# logger.net
KiCad netlist of a schematic drawn in EAGLE
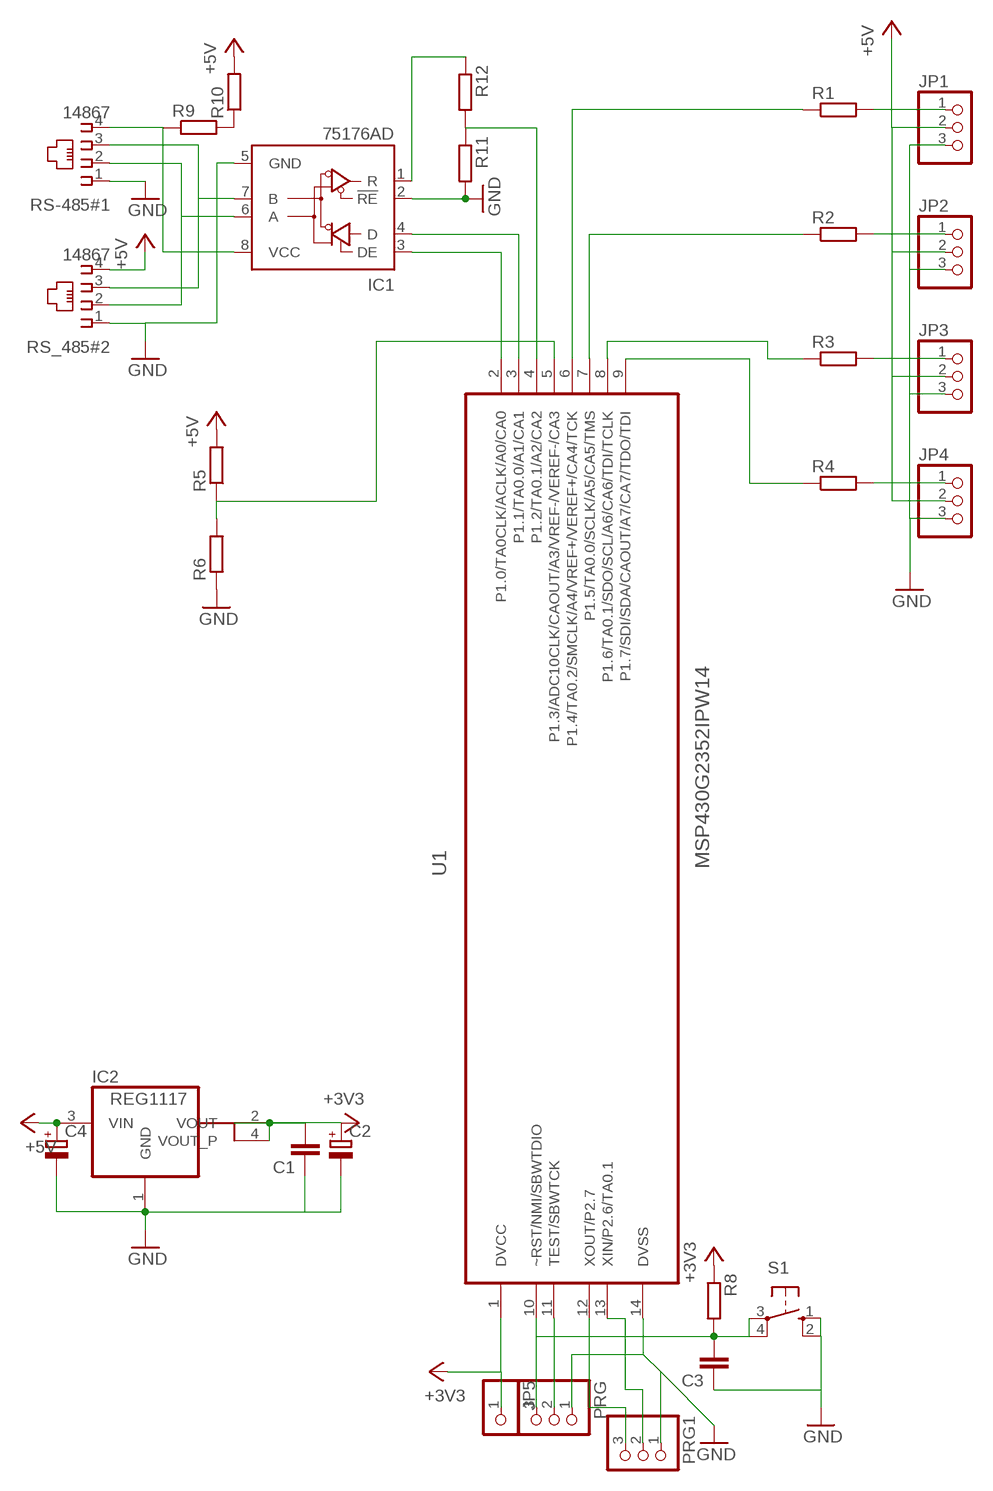
[diagram p0: schematic, sheet 1]

(export (version "E")
  (design (tool "Eeschema 10.0.6"))
  (components
    (comp (ref "C1")
      (value "C-EUC0805")
      (footprint "eagle-import:C0805")
      (libsource (lib "eagle-import") (part "C-EUC0805"))
    )
    (comp (ref "C2")
      (value "CPOL-EUE2,5-6E")
      (footprint "eagle-import:E2,5-6E")
      (libsource (lib "eagle-import") (part "CPOL-EUE2,5-6E"))
    )
    (comp (ref "C3")
      (value "C-EUC0805")
      (footprint "eagle-import:C0805")
      (libsource (lib "eagle-import") (part "C-EUC0805"))
    )
    (comp (ref "C4")
      (value "CPOL-EUE2,5-6E")
      (footprint "eagle-import:E2,5-6E")
      (libsource (lib "eagle-import") (part "CPOL-EUE2,5-6E"))
    )
    (comp (ref "IC1")
      (value "75176AD")
      (footprint "eagle-import:D_R-PDSO-G8")
      (libsource (lib "eagle-import") (part "75176AD"))
    )
    (comp (ref "IC2")
      (value "REG1117")
      (footprint "eagle-import:SOT223")
      (libsource (lib "eagle-import") (part "REG1117"))
    )
    (comp (ref "JP1")
      (value "PINHD-1X3")
      (footprint "eagle-import:1X03")
      (libsource (lib "eagle-import") (part "PINHD-1X3"))
    )
    (comp (ref "JP2")
      (value "PINHD-1X3")
      (footprint "eagle-import:1X03")
      (libsource (lib "eagle-import") (part "PINHD-1X3"))
    )
    (comp (ref "JP3")
      (value "PINHD-1X3")
      (footprint "eagle-import:1X03")
      (libsource (lib "eagle-import") (part "PINHD-1X3"))
    )
    (comp (ref "JP4")
      (value "PINHD-1X3")
      (footprint "eagle-import:1X03")
      (libsource (lib "eagle-import") (part "PINHD-1X3"))
    )
    (comp (ref "JP5")
      (value "PINHD-1X1")
      (footprint "eagle-import:1X01")
      (libsource (lib "eagle-import") (part "PINHD-1X1"))
    )
    (comp (ref "PRG")
      (value "PINHD-1X3")
      (footprint "eagle-import:1X03")
      (libsource (lib "eagle-import") (part "PINHD-1X3"))
    )
    (comp (ref "PRG1")
      (value "PINHD-1X3")
      (footprint "eagle-import:1X03")
      (libsource (lib "eagle-import") (part "PINHD-1X3"))
    )
    (comp (ref "R1")
      (value "R-EU_R0805")
      (footprint "eagle-import:R0805")
      (libsource (lib "eagle-import") (part "R-EU_R0805"))
    )
    (comp (ref "R2")
      (value "R-EU_R0805")
      (footprint "eagle-import:R0805")
      (libsource (lib "eagle-import") (part "R-EU_R0805"))
    )
    (comp (ref "R3")
      (value "R-EU_R0805")
      (footprint "eagle-import:R0805")
      (libsource (lib "eagle-import") (part "R-EU_R0805"))
    )
    (comp (ref "R4")
      (value "R-EU_R0805")
      (footprint "eagle-import:R0805")
      (libsource (lib "eagle-import") (part "R-EU_R0805"))
    )
    (comp (ref "R5")
      (value "R-EU_R0805")
      (footprint "eagle-import:R0805")
      (libsource (lib "eagle-import") (part "R-EU_R0805"))
    )
    (comp (ref "R6")
      (value "R-EU_R0805")
      (footprint "eagle-import:R0805")
      (libsource (lib "eagle-import") (part "R-EU_R0805"))
    )
    (comp (ref "R8")
      (value "R-EU_R0805")
      (footprint "eagle-import:R0805")
      (libsource (lib "eagle-import") (part "R-EU_R0805"))
    )
    (comp (ref "R9")
      (value "R-EU_R1206")
      (footprint "eagle-import:R1206")
      (libsource (lib "eagle-import") (part "R-EU_R1206"))
    )
    (comp (ref "R10")
      (value "R-EU_R1206")
      (footprint "eagle-import:R1206")
      (libsource (lib "eagle-import") (part "R-EU_R1206"))
    )
    (comp (ref "R11")
      (value "R-EU_R0805")
      (footprint "eagle-import:R0805")
      (libsource (lib "eagle-import") (part "R-EU_R0805"))
    )
    (comp (ref "R12")
      (value "R-EU_R0805")
      (footprint "eagle-import:R0805")
      (libsource (lib "eagle-import") (part "R-EU_R0805"))
    )
    (comp (ref "RS-485#1")
      (value "14867")
      (footprint "eagle-import:14867")
      (libsource (lib "eagle-import") (part "14867"))
    )
    (comp (ref "RS_485#2")
      (value "14867")
      (footprint "eagle-import:14867")
      (libsource (lib "eagle-import") (part "14867"))
    )
    (comp (ref "S1")
      (value "10-XX")
      (footprint "eagle-import:B3F-10XX")
      (fields (field (name "MPN") "B3F-1000"))
      (libsource (lib "eagle-import") (part "10-XX"))
    )
    (comp (ref "U1")
      (value "MSP430G2352IPW14")
      (footprint "eagle-import:SOP65P640X120-14N")
      (libsource (lib "eagle-import") (part "MSP430G2352IPW14"))
    )
  )
  (nets
    (net (code "1") (name "+3V3") (class "Default")
      (node (ref "C1") (pin "2") (pinfunction "2_2") (pintype "passive"))
      (node (ref "C2") (pin "+") (pinfunction "+_+") (pintype "passive"))
      (node (ref "IC2") (pin "2") (pinfunction "VOUT_2") (pintype "output"))
      (node (ref "IC2") (pin "4") (pinfunction "VOUT_P_4") (pintype "output"))
      (node (ref "JP5") (pin "1") (pinfunction "1_1") (pintype "passive"))
      (node (ref "R8") (pin "1") (pinfunction "1_1") (pintype "passive"))
      (node (ref "U1") (pin "1") (pinfunction "DVCC_1") (pintype "power_in"))
    )
    (net (code "2") (name "+5V") (class "Default")
      (node (ref "C4") (pin "+") (pinfunction "+_+") (pintype "passive"))
      (node (ref "IC2") (pin "3") (pinfunction "VIN_3") (pintype "input"))
      (node (ref "JP1") (pin "2") (pinfunction "2_2") (pintype "passive"))
      (node (ref "JP2") (pin "2") (pinfunction "2_2") (pintype "passive"))
      (node (ref "JP3") (pin "2") (pinfunction "2_2") (pintype "passive"))
      (node (ref "JP4") (pin "2") (pinfunction "2_2") (pintype "passive"))
      (node (ref "R10") (pin "2") (pinfunction "2_2") (pintype "passive"))
      (node (ref "R5") (pin "2") (pinfunction "2_2") (pintype "passive"))
      (node (ref "RS_485#2") (pin "4") (pinfunction "4_4") (pintype "passive"))
    )
    (net (code "3") (name "GND") (class "Default")
      (node (ref "C1") (pin "1") (pinfunction "1_1") (pintype "passive"))
      (node (ref "C2") (pin "-") (pinfunction "-_-") (pintype "passive"))
      (node (ref "C3") (pin "1") (pinfunction "1_1") (pintype "passive"))
      (node (ref "C4") (pin "-") (pinfunction "-_-") (pintype "passive"))
      (node (ref "IC1") (pin "2") (pinfunction "~{RE}_2") (pintype "input"))
      (node (ref "IC1") (pin "5") (pinfunction "GND_5") (pintype "power_in"))
      (node (ref "IC2") (pin "1") (pinfunction "GND_1") (pintype "power_in"))
      (node (ref "JP1") (pin "3") (pinfunction "3_3") (pintype "passive"))
      (node (ref "JP2") (pin "3") (pinfunction "3_3") (pintype "passive"))
      (node (ref "JP3") (pin "3") (pinfunction "3_3") (pintype "passive"))
      (node (ref "JP4") (pin "3") (pinfunction "3_3") (pintype "passive"))
      (node (ref "PRG") (pin "1") (pinfunction "1_1") (pintype "passive"))
      (node (ref "PRG1") (pin "1") (pinfunction "1_1") (pintype "passive"))
      (node (ref "R11") (pin "2") (pinfunction "2_2") (pintype "passive"))
      (node (ref "R6") (pin "1") (pinfunction "1_1") (pintype "passive"))
      (node (ref "RS-485#1") (pin "1") (pinfunction "1_1") (pintype "passive"))
      (node (ref "RS_485#2") (pin "1") (pinfunction "1_1") (pintype "passive"))
      (node (ref "S1") (pin "1") (pinfunction "S_1") (pintype "passive"))
      (node (ref "S1") (pin "2") (pinfunction "S1_2") (pintype "passive"))
      (node (ref "U1") (pin "14") (pinfunction "DVSS_14") (pintype "power_in"))
    )
    (net (code "4") (name "Net-(IC1-A)") (class "Default")
      (node (ref "IC1") (pin "6") (pinfunction "A_6") (pintype "output"))
      (node (ref "RS-485#1") (pin "2") (pinfunction "2_2") (pintype "passive"))
      (node (ref "RS_485#2") (pin "2") (pinfunction "2_2") (pintype "passive"))
    )
    (net (code "5") (name "Net-(IC1-B)") (class "Default")
      (node (ref "IC1") (pin "7") (pinfunction "B_7") (pintype "output"))
      (node (ref "RS-485#1") (pin "3") (pinfunction "3_3") (pintype "passive"))
      (node (ref "RS_485#2") (pin "3") (pinfunction "3_3") (pintype "passive"))
    )
    (net (code "6") (name "Net-(IC1-D)") (class "Default")
      (node (ref "IC1") (pin "4") (pinfunction "D_4") (pintype "input"))
      (node (ref "U1") (pin "3") (pinfunction "P1.1/TA0.0/A1/CA1_3") (pintype "bidirectional"))
    )
    (net (code "7") (name "Net-(IC1-DE)") (class "Default")
      (node (ref "IC1") (pin "3") (pinfunction "DE_3") (pintype "input"))
      (node (ref "U1") (pin "2") (pinfunction "P1.0/TA0CLK/ACLK/A0/CA0_2") (pintype "bidirectional"))
    )
    (net (code "8") (name "Net-(IC1-R)") (class "Default")
      (node (ref "IC1") (pin "1") (pinfunction "R_1") (pintype "input"))
      (node (ref "R12") (pin "1") (pinfunction "1_1") (pintype "passive"))
    )
    (net (code "9") (name "Net-(IC1-VCC)") (class "Default")
      (node (ref "IC1") (pin "8") (pinfunction "VCC_8") (pintype "power_in"))
      (node (ref "R9") (pin "1") (pinfunction "1_1") (pintype "passive"))
      (node (ref "RS-485#1") (pin "4") (pinfunction "4_4") (pintype "passive"))
    )
    (net (code "10") (name "Net-(JP1-Pad1)") (class "Default")
      (node (ref "JP1") (pin "1") (pinfunction "1_1") (pintype "passive"))
      (node (ref "R1") (pin "2") (pinfunction "2_2") (pintype "passive"))
    )
    (net (code "11") (name "Net-(JP2-Pad1)") (class "Default")
      (node (ref "JP2") (pin "1") (pinfunction "1_1") (pintype "passive"))
      (node (ref "R2") (pin "2") (pinfunction "2_2") (pintype "passive"))
    )
    (net (code "12") (name "Net-(JP3-Pad1)") (class "Default")
      (node (ref "JP3") (pin "1") (pinfunction "1_1") (pintype "passive"))
      (node (ref "R3") (pin "2") (pinfunction "2_2") (pintype "passive"))
    )
    (net (code "13") (name "Net-(JP4-Pad1)") (class "Default")
      (node (ref "JP4") (pin "1") (pinfunction "1_1") (pintype "passive"))
      (node (ref "R4") (pin "2") (pinfunction "2_2") (pintype "passive"))
    )
    (net (code "14") (name "Net-(R10-Pad1)") (class "Default")
      (node (ref "R10") (pin "1") (pinfunction "1_1") (pintype "passive"))
      (node (ref "R9") (pin "2") (pinfunction "2_2") (pintype "passive"))
    )
    (net (code "15") (name "Net-(S1-P)") (class "Default")
      (node (ref "C3") (pin "2") (pinfunction "2_2") (pintype "passive"))
      (node (ref "PRG") (pin "3") (pinfunction "3_3") (pintype "passive"))
      (node (ref "R8") (pin "2") (pinfunction "2_2") (pintype "passive"))
      (node (ref "S1") (pin "3") (pinfunction "P_3") (pintype "passive"))
      (node (ref "S1") (pin "4") (pinfunction "P1_4") (pintype "passive"))
      (node (ref "U1") (pin "10") (pinfunction "~{RST/NMI/SBWTDIO}_10") (pintype "input"))
    )
    (net (code "16") (name "Net-(U1-P1.2{slash}TA0.1{slash}A2{slash}CA2)") (class "Default")
      (node (ref "R11") (pin "1") (pinfunction "1_1") (pintype "passive"))
      (node (ref "R12") (pin "2") (pinfunction "2_2") (pintype "passive"))
      (node (ref "U1") (pin "4") (pinfunction "P1.2/TA0.1/A2/CA2_4") (pintype "bidirectional"))
    )
    (net (code "17") (name "Net-(U1-P1.3{slash}ADC10CLK{slash}CAOUT{slash}A3{slash}VREF-{slash}VEREF-{slash}CA3)") (class "Default")
      (node (ref "R5") (pin "1") (pinfunction "1_1") (pintype "passive"))
      (node (ref "R6") (pin "2") (pinfunction "2_2") (pintype "passive"))
      (node (ref "U1") (pin "5") (pinfunction "P1.3/ADC10CLK/CAOUT/A3/VREF-/VEREF-/CA3_5") (pintype "bidirectional"))
    )
    (net (code "18") (name "Net-(U1-P1.4{slash}TA0.2{slash}SMCLK{slash}A4{slash}VREF+{slash}VEREF+{slash}CA4{slash}TCK)") (class "Default")
      (node (ref "R1") (pin "1") (pinfunction "1_1") (pintype "passive"))
      (node (ref "U1") (pin "6") (pinfunction "P1.4/TA0.2/SMCLK/A4/VREF+/VEREF+/CA4/TCK_6") (pintype "bidirectional"))
    )
    (net (code "19") (name "Net-(U1-P1.5{slash}TA0.0{slash}SCLK{slash}A5{slash}CA5{slash}TMS)") (class "Default")
      (node (ref "R2") (pin "1") (pinfunction "1_1") (pintype "passive"))
      (node (ref "U1") (pin "7") (pinfunction "P1.5/TA0.0/SCLK/A5/CA5/TMS_7") (pintype "bidirectional"))
    )
    (net (code "20") (name "Net-(U1-P1.6{slash}TA0.1{slash}SDO{slash}SCL{slash}A6{slash}CA6{slash}TDI{slash}TCLK)") (class "Default")
      (node (ref "R3") (pin "1") (pinfunction "1_1") (pintype "passive"))
      (node (ref "U1") (pin "8") (pinfunction "P1.6/TA0.1/SDO/SCL/A6/CA6/TDI/TCLK_8") (pintype "bidirectional"))
    )
    (net (code "21") (name "Net-(U1-P1.7{slash}SDI{slash}SDA{slash}CAOUT{slash}A7{slash}CA7{slash}TDO{slash}TDI)") (class "Default")
      (node (ref "R4") (pin "1") (pinfunction "1_1") (pintype "passive"))
      (node (ref "U1") (pin "9") (pinfunction "P1.7/SDI/SDA/CAOUT/A7/CA7/TDO/TDI_9") (pintype "bidirectional"))
    )
    (net (code "22") (name "Net-(U1-TEST{slash}SBWTCK)") (class "Default")
      (node (ref "PRG") (pin "2") (pinfunction "2_2") (pintype "passive"))
      (node (ref "U1") (pin "11") (pinfunction "TEST/SBWTCK_11") (pintype "input"))
    )
    (net (code "23") (name "Net-(U1-XIN{slash}P2.6{slash}TA0.1)") (class "Default")
      (node (ref "PRG1") (pin "2") (pinfunction "2_2") (pintype "passive"))
      (node (ref "U1") (pin "13") (pinfunction "XIN/P2.6/TA0.1_13") (pintype "bidirectional"))
    )
    (net (code "24") (name "Net-(U1-XOUT{slash}P2.7)") (class "Default")
      (node (ref "PRG1") (pin "3") (pinfunction "3_3") (pintype "passive"))
      (node (ref "U1") (pin "12") (pinfunction "XOUT/P2.7_12") (pintype "bidirectional"))
    )
  )
)
